# 7SEG-2.net
KiCad netlist of a schematic drawn in Altium Designer
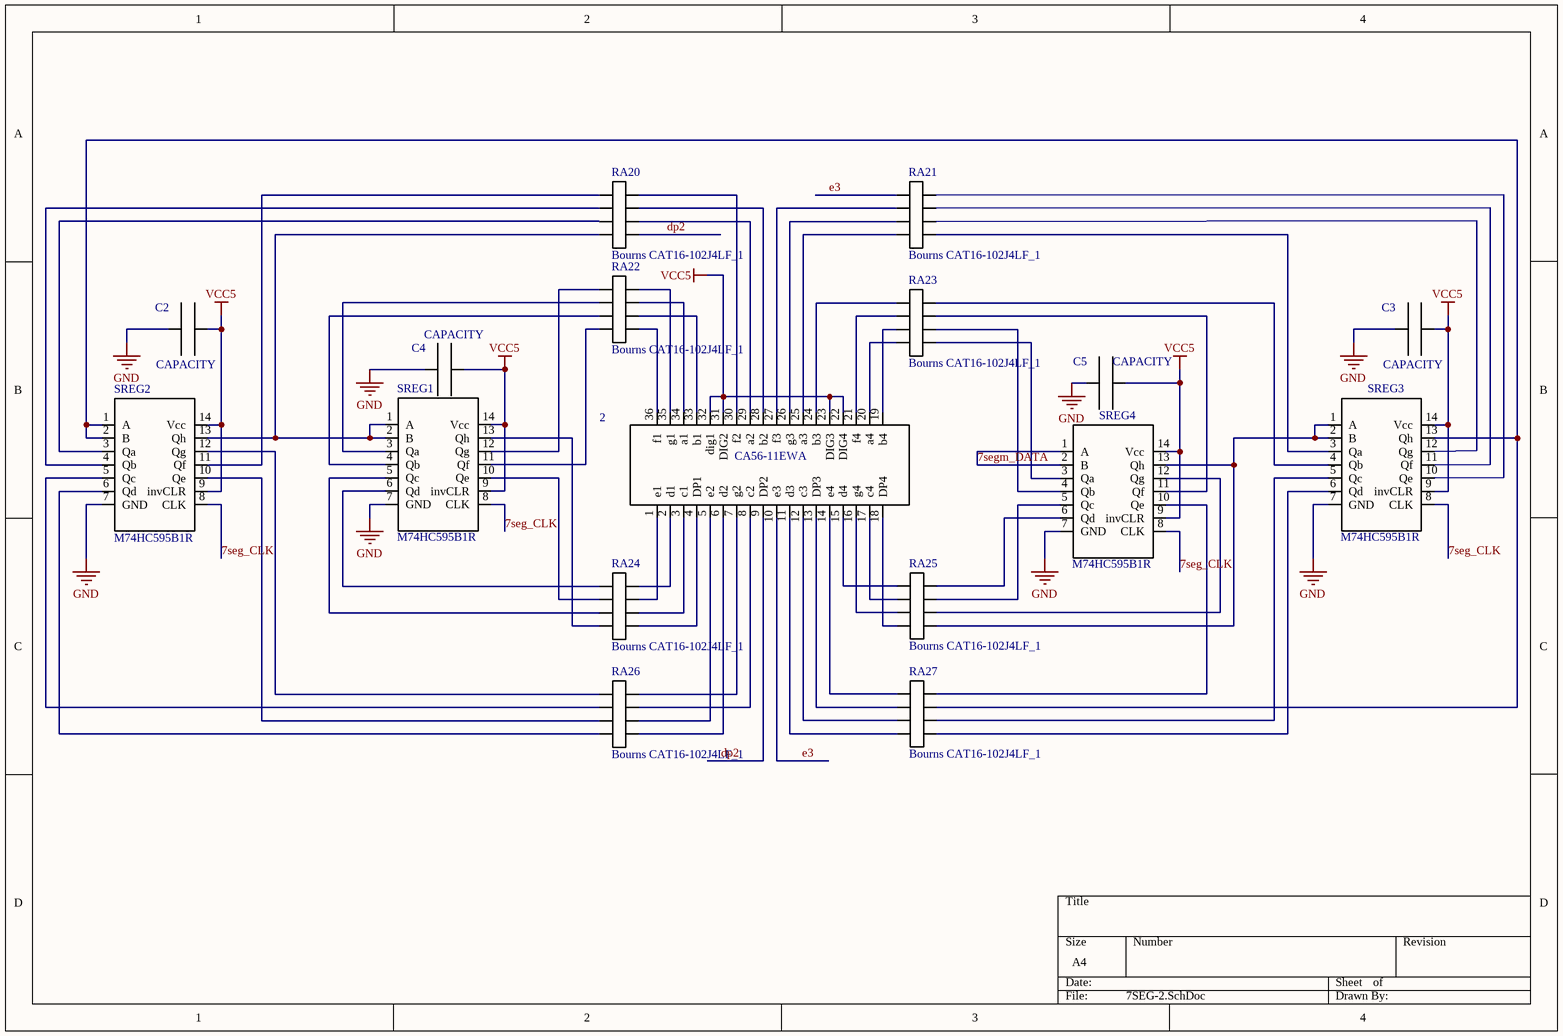
[diagram p0: 7SEG-2.SchDoc]

(export (version "E")
  (design (tool "Eeschema 10.0.6"))
  (components
    (comp (ref "2")
      (value "CA56-11EWA")
      (footprint "PcbLib1:CA56-11EWA")
      (libsource (lib "Library") (part "CA56-11EWA"))
    )
    (comp (ref "C2")
      (value "CAPACITY")
      (footprint "PcbLib1:R0805")
      (libsource (lib "Library") (part "CAPACITY"))
    )
    (comp (ref "C3")
      (value "CAPACITY")
      (footprint "PcbLib1:R0805")
      (libsource (lib "Library") (part "CAPACITY"))
    )
    (comp (ref "C4")
      (value "CAPACITY")
      (footprint "PcbLib1:R0805")
      (libsource (lib "Library") (part "CAPACITY"))
    )
    (comp (ref "C5")
      (value "CAPACITY")
      (footprint "PcbLib1:R0805")
      (libsource (lib "Library") (part "CAPACITY"))
    )
    (comp (ref "RA20")
      (value "Bourns CAT16-102J4LF_1")
      (footprint "PcbLib1:CAT16-102J4LF_2")
      (libsource (lib "Library") (part "Bourns CAT16-102J4LF_1"))
    )
    (comp (ref "RA21")
      (value "Bourns CAT16-102J4LF_1")
      (footprint "PcbLib1:CAT16-102J4LF_2")
      (libsource (lib "Library") (part "Bourns CAT16-102J4LF_1"))
    )
    (comp (ref "RA22")
      (value "Bourns CAT16-102J4LF_1")
      (footprint "PcbLib1:CAT16-102J4LF_2")
      (libsource (lib "Library") (part "Bourns CAT16-102J4LF_1"))
    )
    (comp (ref "RA23")
      (value "Bourns CAT16-102J4LF_1")
      (footprint "PcbLib1:CAT16-102J4LF_2")
      (libsource (lib "Library") (part "Bourns CAT16-102J4LF_1"))
    )
    (comp (ref "RA24")
      (value "Bourns CAT16-102J4LF_1")
      (footprint "PcbLib1:CAT16-102J4LF_2")
      (libsource (lib "Library") (part "Bourns CAT16-102J4LF_1"))
    )
    (comp (ref "RA25")
      (value "Bourns CAT16-102J4LF_1")
      (footprint "PcbLib1:CAT16-102J4LF_2")
      (libsource (lib "Library") (part "Bourns CAT16-102J4LF_1"))
    )
    (comp (ref "RA26")
      (value "Bourns CAT16-102J4LF_1")
      (footprint "PcbLib1:CAT16-102J4LF_2")
      (libsource (lib "Library") (part "Bourns CAT16-102J4LF_1"))
    )
    (comp (ref "RA27")
      (value "Bourns CAT16-102J4LF_1")
      (footprint "PcbLib1:CAT16-102J4LF_2")
      (libsource (lib "Library") (part "Bourns CAT16-102J4LF_1"))
    )
    (comp (ref "SREG1")
      (value "M74HC595B1R")
      (footprint "PcbLib1:SN74HC164DRX")
      (libsource (lib "Library") (part "M74HC595B1R"))
    )
    (comp (ref "SREG2")
      (value "M74HC595B1R")
      (footprint "PcbLib1:SN74HC164DRX")
      (libsource (lib "Library") (part "M74HC595B1R"))
    )
    (comp (ref "SREG3")
      (value "M74HC595B1R")
      (footprint "PcbLib1:SN74HC164DRX")
      (libsource (lib "Library") (part "M74HC595B1R"))
    )
    (comp (ref "SREG4")
      (value "M74HC595B1R")
      (footprint "PcbLib1:SN74HC164DRX")
      (libsource (lib "Library") (part "M74HC595B1R"))
    )
  )
  (nets
    (net (code "1") (name "/7seg_CLK") (class "Default")
      (node (ref "SREG1") (pin "8") (pinfunction "CLK_8") (pintype "passive"))
      (node (ref "SREG2") (pin "8") (pinfunction "CLK_8") (pintype "passive"))
      (node (ref "SREG3") (pin "8") (pinfunction "CLK_8") (pintype "passive"))
      (node (ref "SREG4") (pin "8") (pinfunction "CLK_8") (pintype "passive"))
    )
    (net (code "2") (name "/7segm_DATA") (class "Default")
      (node (ref "SREG4") (pin "1") (pinfunction "A_1") (pintype "passive"))
      (node (ref "SREG4") (pin "2") (pinfunction "B_2") (pintype "passive"))
    )
    (net (code "3") (name "/dp2") (class "Default")
      (node (ref "2") (pin "9") (pinfunction "DP2_9") (pintype "passive"))
      (node (ref "RA20") (pin "3") (pinfunction "3_3") (pintype "passive"))
    )
    (net (code "4") (name "/e3") (class "Default")
      (node (ref "2") (pin "10") (pinfunction "e3_10") (pintype "passive"))
      (node (ref "RA21") (pin "3") (pinfunction "3_3") (pintype "passive"))
    )
    (net (code "5") (name "GND") (class "Default")
      (node (ref "C2") (pin "1") (pinfunction "1_1") (pintype "passive"))
      (node (ref "C3") (pin "1") (pinfunction "1_1") (pintype "passive"))
      (node (ref "C4") (pin "1") (pinfunction "1_1") (pintype "passive"))
      (node (ref "C5") (pin "1") (pinfunction "1_1") (pintype "passive"))
      (node (ref "SREG1") (pin "7") (pinfunction "GND_7") (pintype "passive"))
      (node (ref "SREG2") (pin "7") (pinfunction "GND_7") (pintype "passive"))
      (node (ref "SREG3") (pin "7") (pinfunction "GND_7") (pintype "passive"))
      (node (ref "SREG4") (pin "7") (pinfunction "GND_7") (pintype "passive"))
    )
    (net (code "6") (name "Net-(2-DP1)") (class "Default")
      (node (ref "2") (pin "4") (pinfunction "DP1_4") (pintype "passive"))
      (node (ref "RA24") (pin "4") (pinfunction "4_4") (pintype "passive"))
    )
    (net (code "7") (name "Net-(2-DP3)") (class "Default")
      (node (ref "2") (pin "13") (pinfunction "DP3_13") (pintype "passive"))
      (node (ref "RA27") (pin "6") (pinfunction "6_6") (pintype "passive"))
    )
    (net (code "8") (name "Net-(2-DP4)") (class "Default")
      (node (ref "2") (pin "18") (pinfunction "DP4_18") (pintype "passive"))
      (node (ref "RA25") (pin "7") (pinfunction "7_7") (pintype "passive"))
    )
    (net (code "9") (name "Net-(2-a1)") (class "Default")
      (node (ref "2") (pin "34") (pinfunction "a1_34") (pintype "passive"))
      (node (ref "RA22") (pin "2") (pinfunction "2_2") (pintype "passive"))
    )
    (net (code "10") (name "Net-(2-a2)") (class "Default")
      (node (ref "2") (pin "29") (pinfunction "a2_29") (pintype "passive"))
      (node (ref "RA20") (pin "2") (pinfunction "2_2") (pintype "passive"))
    )
    (net (code "11") (name "Net-(2-a3)") (class "Default")
      (node (ref "2") (pin "25") (pinfunction "a3_25") (pintype "passive"))
      (node (ref "RA21") (pin "0") (pinfunction "0_0") (pintype "passive"))
    )
    (net (code "12") (name "Net-(2-a4)") (class "Default")
      (node (ref "2") (pin "20") (pinfunction "a4_20") (pintype "passive"))
      (node (ref "RA23") (pin "0") (pinfunction "0_0") (pintype "passive"))
    )
    (net (code "13") (name "Net-(2-b1)") (class "Default")
      (node (ref "2") (pin "33") (pinfunction "b1_33") (pintype "passive"))
      (node (ref "RA22") (pin "1") (pinfunction "1_1") (pintype "passive"))
    )
    (net (code "14") (name "Net-(2-b2)") (class "Default")
      (node (ref "2") (pin "28") (pinfunction "b2_28") (pintype "passive"))
      (node (ref "RA20") (pin "1") (pinfunction "1_1") (pintype "passive"))
    )
    (net (code "15") (name "Net-(2-b3)") (class "Default")
      (node (ref "2") (pin "24") (pinfunction "b3_24") (pintype "passive"))
      (node (ref "RA23") (pin "3") (pinfunction "3_3") (pintype "passive"))
    )
    (net (code "16") (name "Net-(2-b4)") (class "Default")
      (node (ref "2") (pin "19") (pinfunction "b4_19") (pintype "passive"))
      (node (ref "RA23") (pin "1") (pinfunction "1_1") (pintype "passive"))
    )
    (net (code "17") (name "Net-(2-c1)") (class "Default")
      (node (ref "2") (pin "3") (pinfunction "c1_3") (pintype "passive"))
      (node (ref "RA24") (pin "5") (pinfunction "5_5") (pintype "passive"))
    )
    (net (code "18") (name "Net-(2-c2)") (class "Default")
      (node (ref "2") (pin "8") (pinfunction "c2_8") (pintype "passive"))
      (node (ref "RA26") (pin "5") (pinfunction "5_5") (pintype "passive"))
    )
    (net (code "19") (name "Net-(2-c3)") (class "Default")
      (node (ref "2") (pin "12") (pinfunction "c3_12") (pintype "passive"))
      (node (ref "RA27") (pin "5") (pinfunction "5_5") (pintype "passive"))
    )
    (net (code "20") (name "Net-(2-c4)") (class "Default")
      (node (ref "2") (pin "17") (pinfunction "c4_17") (pintype "passive"))
      (node (ref "RA25") (pin "5") (pinfunction "5_5") (pintype "passive"))
    )
    (net (code "21") (name "Net-(2-d1)") (class "Default")
      (node (ref "2") (pin "2") (pinfunction "d1_2") (pintype "passive"))
      (node (ref "RA24") (pin "7") (pinfunction "7_7") (pintype "passive"))
    )
    (net (code "22") (name "Net-(2-d2)") (class "Default")
      (node (ref "2") (pin "6") (pinfunction "d2_6") (pintype "passive"))
      (node (ref "RA26") (pin "7") (pinfunction "7_7") (pintype "passive"))
    )
    (net (code "23") (name "Net-(2-d3)") (class "Default")
      (node (ref "2") (pin "11") (pinfunction "d3_11") (pintype "passive"))
      (node (ref "RA27") (pin "4") (pinfunction "4_4") (pintype "passive"))
    )
    (net (code "24") (name "Net-(2-d4)") (class "Default")
      (node (ref "2") (pin "15") (pinfunction "d4_15") (pintype "passive"))
      (node (ref "RA25") (pin "4") (pinfunction "4_4") (pintype "passive"))
    )
    (net (code "25") (name "Net-(2-e1)") (class "Default")
      (node (ref "2") (pin "1") (pinfunction "e1_1") (pintype "passive"))
      (node (ref "RA24") (pin "6") (pinfunction "6_6") (pintype "passive"))
    )
    (net (code "26") (name "Net-(2-e2)") (class "Default")
      (node (ref "2") (pin "5") (pinfunction "e2_5") (pintype "passive"))
      (node (ref "RA26") (pin "6") (pinfunction "6_6") (pintype "passive"))
    )
    (net (code "27") (name "Net-(2-e4)") (class "Default")
      (node (ref "2") (pin "14") (pinfunction "e4_14") (pintype "passive"))
      (node (ref "RA27") (pin "7") (pinfunction "7_7") (pintype "passive"))
    )
    (net (code "28") (name "Net-(2-f1)") (class "Default")
      (node (ref "2") (pin "36") (pinfunction "f1_36") (pintype "passive"))
      (node (ref "RA22") (pin "0") (pinfunction "0_0") (pintype "passive"))
    )
    (net (code "29") (name "Net-(2-f2)") (class "Default")
      (node (ref "2") (pin "30") (pinfunction "f2_30") (pintype "passive"))
      (node (ref "RA20") (pin "0") (pinfunction "0_0") (pintype "passive"))
    )
    (net (code "30") (name "Net-(2-f3)") (class "Default")
      (node (ref "2") (pin "27") (pinfunction "f3_27") (pintype "passive"))
      (node (ref "RA21") (pin "2") (pinfunction "2_2") (pintype "passive"))
    )
    (net (code "31") (name "Net-(2-f4)") (class "Default")
      (node (ref "2") (pin "21") (pinfunction "f4_21") (pintype "passive"))
      (node (ref "RA23") (pin "2") (pinfunction "2_2") (pintype "passive"))
    )
    (net (code "32") (name "Net-(2-g1)") (class "Default")
      (node (ref "2") (pin "35") (pinfunction "g1_35") (pintype "passive"))
      (node (ref "RA22") (pin "3") (pinfunction "3_3") (pintype "passive"))
    )
    (net (code "33") (name "Net-(2-g2)") (class "Default")
      (node (ref "2") (pin "7") (pinfunction "g2_7") (pintype "passive"))
      (node (ref "RA26") (pin "4") (pinfunction "4_4") (pintype "passive"))
    )
    (net (code "34") (name "Net-(2-g3)") (class "Default")
      (node (ref "2") (pin "26") (pinfunction "g3_26") (pintype "passive"))
      (node (ref "RA21") (pin "1") (pinfunction "1_1") (pintype "passive"))
    )
    (net (code "35") (name "Net-(2-g4)") (class "Default")
      (node (ref "2") (pin "16") (pinfunction "g4_16") (pintype "passive"))
      (node (ref "RA25") (pin "6") (pinfunction "6_6") (pintype "passive"))
    )
    (net (code "36") (name "Net-(SREG1-A)") (class "Default")
      (node (ref "RA20") (pin "4") (pinfunction "4_4") (pintype "passive"))
      (node (ref "SREG1") (pin "1") (pinfunction "A_1") (pintype "passive"))
      (node (ref "SREG1") (pin "2") (pinfunction "B_2") (pintype "passive"))
      (node (ref "SREG2") (pin "13") (pinfunction "Qh_13") (pintype "passive"))
    )
    (net (code "37") (name "Net-(SREG1-Qa)") (class "Default")
      (node (ref "RA22") (pin "5") (pinfunction "5_5") (pintype "passive"))
      (node (ref "SREG1") (pin "3") (pinfunction "Qa_3") (pintype "passive"))
    )
    (net (code "38") (name "Net-(SREG1-Qb)") (class "Default")
      (node (ref "RA22") (pin "6") (pinfunction "6_6") (pintype "passive"))
      (node (ref "SREG1") (pin "4") (pinfunction "Qb_4") (pintype "passive"))
    )
    (net (code "39") (name "Net-(SREG1-Qc)") (class "Default")
      (node (ref "RA24") (pin "2") (pinfunction "2_2") (pintype "passive"))
      (node (ref "SREG1") (pin "5") (pinfunction "Qc_5") (pintype "passive"))
    )
    (net (code "40") (name "Net-(SREG1-Qd)") (class "Default")
      (node (ref "RA24") (pin "0") (pinfunction "0_0") (pintype "passive"))
      (node (ref "SREG1") (pin "6") (pinfunction "Qd_6") (pintype "passive"))
    )
    (net (code "41") (name "Net-(SREG1-Qe)") (class "Default")
      (node (ref "RA24") (pin "1") (pinfunction "1_1") (pintype "passive"))
      (node (ref "SREG1") (pin "10") (pinfunction "Qe_10") (pintype "passive"))
    )
    (net (code "42") (name "Net-(SREG1-Qf)") (class "Default")
      (node (ref "RA22") (pin "7") (pinfunction "7_7") (pintype "passive"))
      (node (ref "SREG1") (pin "11") (pinfunction "Qf_11") (pintype "passive"))
    )
    (net (code "43") (name "Net-(SREG1-Qg)") (class "Default")
      (node (ref "RA22") (pin "4") (pinfunction "4_4") (pintype "passive"))
      (node (ref "SREG1") (pin "12") (pinfunction "Qg_12") (pintype "passive"))
    )
    (net (code "44") (name "Net-(SREG1-Qh)") (class "Default")
      (node (ref "RA24") (pin "3") (pinfunction "3_3") (pintype "passive"))
      (node (ref "SREG1") (pin "13") (pinfunction "Qh_13") (pintype "passive"))
    )
    (net (code "45") (name "Net-(SREG2-A)") (class "Default")
      (node (ref "RA27") (pin "1") (pinfunction "1_1") (pintype "passive"))
      (node (ref "SREG2") (pin "1") (pinfunction "A_1") (pintype "passive"))
      (node (ref "SREG2") (pin "2") (pinfunction "B_2") (pintype "passive"))
      (node (ref "SREG3") (pin "13") (pinfunction "Qh_13") (pintype "passive"))
    )
    (net (code "46") (name "Net-(SREG2-Qa)") (class "Default")
      (node (ref "RA20") (pin "5") (pinfunction "5_5") (pintype "passive"))
      (node (ref "SREG2") (pin "3") (pinfunction "Qa_3") (pintype "passive"))
    )
    (net (code "47") (name "Net-(SREG2-Qb)") (class "Default")
      (node (ref "RA20") (pin "6") (pinfunction "6_6") (pintype "passive"))
      (node (ref "SREG2") (pin "4") (pinfunction "Qb_4") (pintype "passive"))
    )
    (net (code "48") (name "Net-(SREG2-Qc)") (class "Default")
      (node (ref "RA26") (pin "2") (pinfunction "2_2") (pintype "passive"))
      (node (ref "SREG2") (pin "5") (pinfunction "Qc_5") (pintype "passive"))
    )
    (net (code "49") (name "Net-(SREG2-Qd)") (class "Default")
      (node (ref "RA26") (pin "0") (pinfunction "0_0") (pintype "passive"))
      (node (ref "SREG2") (pin "6") (pinfunction "Qd_6") (pintype "passive"))
    )
    (net (code "50") (name "Net-(SREG2-Qe)") (class "Default")
      (node (ref "RA26") (pin "1") (pinfunction "1_1") (pintype "passive"))
      (node (ref "SREG2") (pin "10") (pinfunction "Qe_10") (pintype "passive"))
    )
    (net (code "51") (name "Net-(SREG2-Qf)") (class "Default")
      (node (ref "RA20") (pin "7") (pinfunction "7_7") (pintype "passive"))
      (node (ref "SREG2") (pin "11") (pinfunction "Qf_11") (pintype "passive"))
    )
    (net (code "52") (name "Net-(SREG2-Qg)") (class "Default")
      (node (ref "RA26") (pin "3") (pinfunction "3_3") (pintype "passive"))
      (node (ref "SREG2") (pin "12") (pinfunction "Qg_12") (pintype "passive"))
    )
    (net (code "53") (name "Net-(SREG3-A)") (class "Default")
      (node (ref "RA25") (pin "0") (pinfunction "0_0") (pintype "passive"))
      (node (ref "SREG3") (pin "1") (pinfunction "A_1") (pintype "passive"))
      (node (ref "SREG3") (pin "2") (pinfunction "B_2") (pintype "passive"))
      (node (ref "SREG4") (pin "13") (pinfunction "Qh_13") (pintype "passive"))
    )
    (net (code "54") (name "Net-(SREG3-Qa)") (class "Default")
      (node (ref "RA21") (pin "7") (pinfunction "7_7") (pintype "passive"))
      (node (ref "SREG3") (pin "3") (pinfunction "Qa_3") (pintype "passive"))
    )
    (net (code "55") (name "Net-(SREG3-Qb)") (class "Default")
      (node (ref "RA23") (pin "4") (pinfunction "4_4") (pintype "passive"))
      (node (ref "SREG3") (pin "4") (pinfunction "Qb_4") (pintype "passive"))
    )
    (net (code "56") (name "Net-(SREG3-Qc)") (class "Default")
      (node (ref "RA27") (pin "2") (pinfunction "2_2") (pintype "passive"))
      (node (ref "SREG3") (pin "5") (pinfunction "Qc_5") (pintype "passive"))
    )
    (net (code "57") (name "Net-(SREG3-Qd)") (class "Default")
      (node (ref "RA27") (pin "3") (pinfunction "3_3") (pintype "passive"))
      (node (ref "SREG3") (pin "6") (pinfunction "Qd_6") (pintype "passive"))
    )
    (net (code "58") (name "Net-(SREG3-Qe)") (class "Default")
      (node (ref "RA21") (pin "4") (pinfunction "4_4") (pintype "passive"))
      (node (ref "SREG3") (pin "10") (pinfunction "Qe_10") (pintype "passive"))
    )
    (net (code "59") (name "Net-(SREG3-Qf)") (class "Default")
      (node (ref "RA21") (pin "5") (pinfunction "5_5") (pintype "passive"))
      (node (ref "SREG3") (pin "11") (pinfunction "Qf_11") (pintype "passive"))
    )
    (net (code "60") (name "Net-(SREG3-Qg)") (class "Default")
      (node (ref "RA21") (pin "6") (pinfunction "6_6") (pintype "passive"))
      (node (ref "SREG3") (pin "12") (pinfunction "Qg_12") (pintype "passive"))
    )
    (net (code "61") (name "Net-(SREG4-Qa)") (class "Default")
      (node (ref "RA23") (pin "7") (pinfunction "7_7") (pintype "passive"))
      (node (ref "SREG4") (pin "3") (pinfunction "Qa_3") (pintype "passive"))
    )
    (net (code "62") (name "Net-(SREG4-Qb)") (class "Default")
      (node (ref "RA23") (pin "6") (pinfunction "6_6") (pintype "passive"))
      (node (ref "SREG4") (pin "4") (pinfunction "Qb_4") (pintype "passive"))
    )
    (net (code "63") (name "Net-(SREG4-Qc)") (class "Default")
      (node (ref "RA25") (pin "2") (pinfunction "2_2") (pintype "passive"))
      (node (ref "SREG4") (pin "5") (pinfunction "Qc_5") (pintype "passive"))
    )
    (net (code "64") (name "Net-(SREG4-Qd)") (class "Default")
      (node (ref "RA25") (pin "3") (pinfunction "3_3") (pintype "passive"))
      (node (ref "SREG4") (pin "6") (pinfunction "Qd_6") (pintype "passive"))
    )
    (net (code "65") (name "Net-(SREG4-Qe)") (class "Default")
      (node (ref "RA27") (pin "0") (pinfunction "0_0") (pintype "passive"))
      (node (ref "SREG4") (pin "10") (pinfunction "Qe_10") (pintype "passive"))
    )
    (net (code "66") (name "Net-(SREG4-Qf)") (class "Default")
      (node (ref "RA23") (pin "5") (pinfunction "5_5") (pintype "passive"))
      (node (ref "SREG4") (pin "11") (pinfunction "Qf_11") (pintype "passive"))
    )
    (net (code "67") (name "Net-(SREG4-Qg)") (class "Default")
      (node (ref "RA25") (pin "1") (pinfunction "1_1") (pintype "passive"))
      (node (ref "SREG4") (pin "12") (pinfunction "Qg_12") (pintype "passive"))
    )
    (net (code "68") (name "VCC5") (class "Default")
      (node (ref "2") (pin "22") (pinfunction "DIG4_22") (pintype "passive"))
      (node (ref "2") (pin "23") (pinfunction "DIG3_23") (pintype "passive"))
      (node (ref "2") (pin "31") (pinfunction "DIG2_31") (pintype "passive"))
      (node (ref "2") (pin "32") (pinfunction "dig1_32") (pintype "passive"))
      (node (ref "C2") (pin "2") (pinfunction "2_2") (pintype "passive"))
      (node (ref "C3") (pin "2") (pinfunction "2_2") (pintype "passive"))
      (node (ref "C4") (pin "2") (pinfunction "2_2") (pintype "passive"))
      (node (ref "C5") (pin "2") (pinfunction "2_2") (pintype "passive"))
      (node (ref "SREG1") (pin "14") (pinfunction "Vcc_14") (pintype "passive"))
      (node (ref "SREG1") (pin "9") (pinfunction "invCLR_9") (pintype "passive"))
      (node (ref "SREG2") (pin "14") (pinfunction "Vcc_14") (pintype "passive"))
      (node (ref "SREG2") (pin "9") (pinfunction "invCLR_9") (pintype "passive"))
      (node (ref "SREG3") (pin "14") (pinfunction "Vcc_14") (pintype "passive"))
      (node (ref "SREG3") (pin "9") (pinfunction "invCLR_9") (pintype "passive"))
      (node (ref "SREG4") (pin "14") (pinfunction "Vcc_14") (pintype "passive"))
      (node (ref "SREG4") (pin "9") (pinfunction "invCLR_9") (pintype "passive"))
    )
  )
)
